# atx_power_control.net
KiCad netlist of a schematic drawn in EAGLE
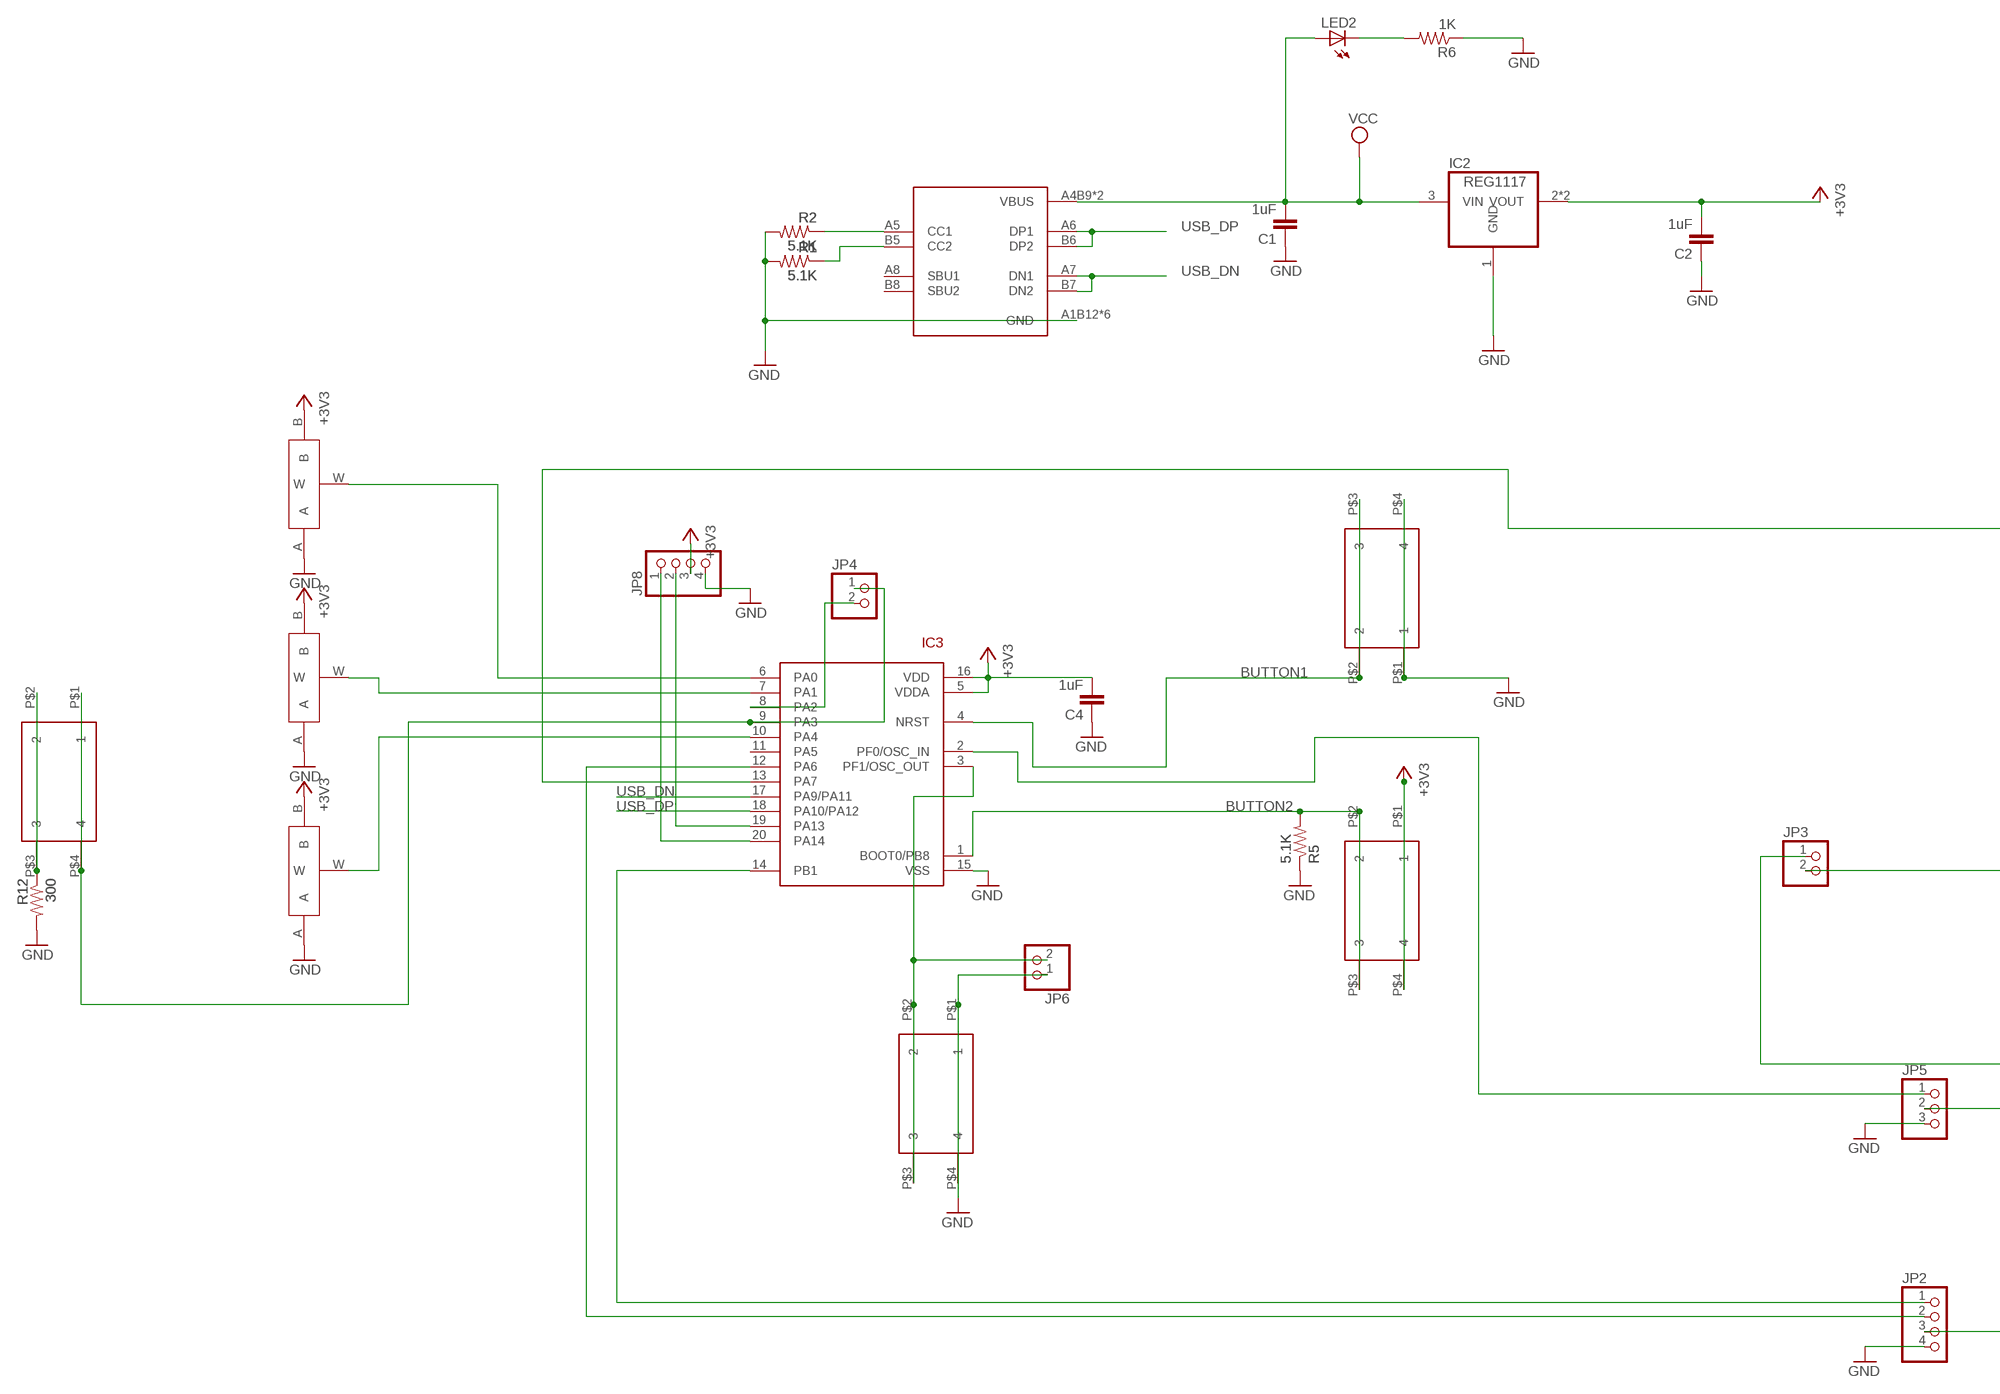
[diagram p0: schematic, sheet 1, part 1 of 2]
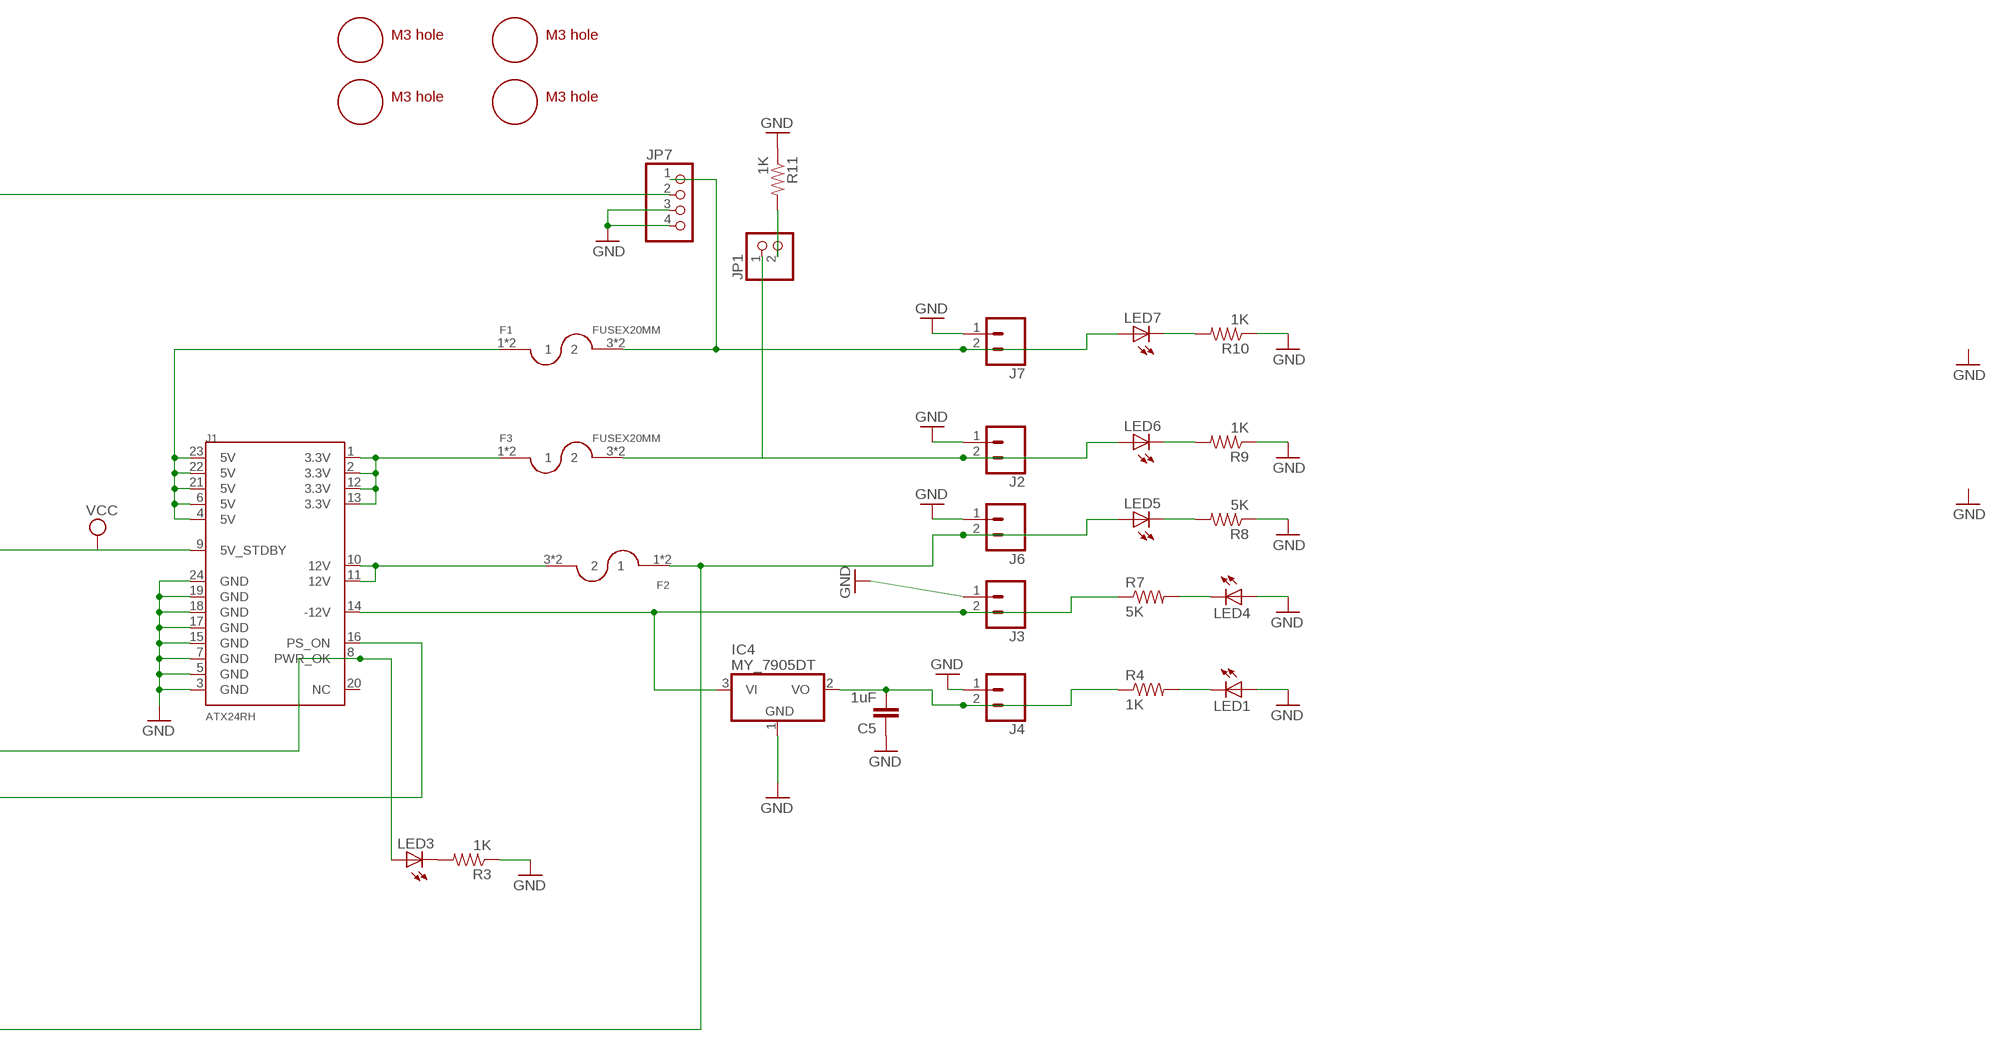
[diagram p1: schematic, sheet 1, part 2 of 2]

(export (version "E")
  (design (tool "Eeschema 10.0.6"))
  (components
    (comp (ref "C1")
      (value "1uF")
      (footprint "eagle-import:0805@1")
      (libsource (lib "eagle-import") (part "CAP0805"))
    )
    (comp (ref "C2")
      (value "1uF")
      (footprint "eagle-import:0805@1")
      (libsource (lib "eagle-import") (part "CAP0805"))
    )
    (comp (ref "C4")
      (value "1uF")
      (footprint "eagle-import:0805@1")
      (libsource (lib "eagle-import") (part "CAP0805"))
    )
    (comp (ref "C5")
      (value "1uF")
      (footprint "eagle-import:0805@1")
      (libsource (lib "eagle-import") (part "CAP0805"))
    )
    (comp (ref "F1")
      (value "FUSEX20MM")
      (footprint "eagle-import:FUSE_5MM")
      (libsource (lib "eagle-import") (part "FUSEX20MM"))
    )
    (comp (ref "F2")
      (value "FUSEX20MM")
      (footprint "eagle-import:FUSE_5MM")
      (libsource (lib "eagle-import") (part "FUSEX20MM"))
    )
    (comp (ref "F3")
      (value "FUSEX20MM")
      (footprint "eagle-import:FUSE_5MM")
      (libsource (lib "eagle-import") (part "FUSEX20MM"))
    )
    (comp (ref "IC2")
      (value "REG1117")
      (footprint "eagle-import:SOT223")
      (libsource (lib "eagle-import") (part "REG1117"))
    )
    (comp (ref "IC3")
      (value "STM32F042F4")
      (footprint "eagle-import:TSSOP20")
      (libsource (lib "eagle-import") (part "STM32F042F4"))
    )
    (comp (ref "IC4")
      (value "MY_7905DT")
      (footprint "eagle-import:ADAFRUIT_TO252")
      (libsource (lib "eagle-import") (part "MY_7905DT"))
    )
    (comp (ref "J1")
      (value "ATX24RH")
      (footprint "eagle-import:ATX24_RIGHT_ANGLE")
      (libsource (lib "eagle-import") (part "ATX24RH"))
    )
    (comp (ref "J2")
      (value "CONN_023.5MM")
      (footprint "eagle-import:SCREWTERMINAL-3.5MM-2")
      (libsource (lib "eagle-import") (part "CONN_023.5MM"))
    )
    (comp (ref "J3")
      (value "CONN_023.5MM")
      (footprint "eagle-import:SCREWTERMINAL-3.5MM-2")
      (libsource (lib "eagle-import") (part "CONN_023.5MM"))
    )
    (comp (ref "J4")
      (value "CONN_023.5MM")
      (footprint "eagle-import:SCREWTERMINAL-3.5MM-2")
      (libsource (lib "eagle-import") (part "CONN_023.5MM"))
    )
    (comp (ref "J6")
      (value "CONN_023.5MM")
      (footprint "eagle-import:SCREWTERMINAL-3.5MM-2")
      (libsource (lib "eagle-import") (part "CONN_023.5MM"))
    )
    (comp (ref "J7")
      (value "CONN_023.5MM")
      (footprint "eagle-import:SCREWTERMINAL-3.5MM-2")
      (libsource (lib "eagle-import") (part "CONN_023.5MM"))
    )
    (comp (ref "JP1")
      (value "PINHD-1X2")
      (footprint "eagle-import:1X02")
      (libsource (lib "eagle-import") (part "PINHD-1X2"))
    )
    (comp (ref "JP2")
      (value "PINHD-1X4")
      (footprint "eagle-import:1X04")
      (libsource (lib "eagle-import") (part "PINHD-1X4"))
    )
    (comp (ref "JP3")
      (value "PINHD-1X2")
      (footprint "eagle-import:1X02")
      (libsource (lib "eagle-import") (part "PINHD-1X2"))
    )
    (comp (ref "JP4")
      (value "PINHD-1X2")
      (footprint "eagle-import:1X02")
      (libsource (lib "eagle-import") (part "PINHD-1X2"))
    )
    (comp (ref "JP5")
      (value "PINHD-1X3")
      (footprint "eagle-import:1X03")
      (libsource (lib "eagle-import") (part "PINHD-1X3"))
    )
    (comp (ref "JP6")
      (value "PINHD-1X2")
      (footprint "eagle-import:1X02")
      (libsource (lib "eagle-import") (part "PINHD-1X2"))
    )
    (comp (ref "JP7")
      (value "PINHD-1X4")
      (footprint "eagle-import:1X04")
      (libsource (lib "eagle-import") (part "PINHD-1X4"))
    )
    (comp (ref "JP8")
      (value "PINHD-1X4")
      (footprint "eagle-import:1X04")
      (libsource (lib "eagle-import") (part "PINHD-1X4"))
    )
    (comp (ref "LED1")
      (value "LEDCHIP-LED0805")
      (footprint "eagle-import:CHIP-LED0805")
      (libsource (lib "eagle-import") (part "LEDCHIP-LED0805"))
    )
    (comp (ref "LED2")
      (value "LEDCHIP-LED0805")
      (footprint "eagle-import:CHIP-LED0805")
      (libsource (lib "eagle-import") (part "LEDCHIP-LED0805"))
    )
    (comp (ref "LED3")
      (value "LEDCHIP-LED0805")
      (footprint "eagle-import:CHIP-LED0805")
      (libsource (lib "eagle-import") (part "LEDCHIP-LED0805"))
    )
    (comp (ref "LED4")
      (value "LEDCHIP-LED0805")
      (footprint "eagle-import:CHIP-LED0805")
      (libsource (lib "eagle-import") (part "LEDCHIP-LED0805"))
    )
    (comp (ref "LED5")
      (value "LEDCHIP-LED0805")
      (footprint "eagle-import:CHIP-LED0805")
      (libsource (lib "eagle-import") (part "LEDCHIP-LED0805"))
    )
    (comp (ref "LED6")
      (value "LEDCHIP-LED0805")
      (footprint "eagle-import:CHIP-LED0805")
      (libsource (lib "eagle-import") (part "LEDCHIP-LED0805"))
    )
    (comp (ref "LED7")
      (value "LEDCHIP-LED0805")
      (footprint "eagle-import:CHIP-LED0805")
      (libsource (lib "eagle-import") (part "LEDCHIP-LED0805"))
    )
    (comp (ref "R1")
      (value "5.1K")
      (footprint "eagle-import:0805")
      (libsource (lib "eagle-import") (part "joyAnalog_RESISTOR0805-RES"))
    )
    (comp (ref "R2")
      (value "5.1K")
      (footprint "eagle-import:0805")
      (libsource (lib "eagle-import") (part "joyAnalog_RESISTOR0805-RES"))
    )
    (comp (ref "R3")
      (value "1K")
      (footprint "eagle-import:0805")
      (libsource (lib "eagle-import") (part "RESISTOR0805-RES"))
    )
    (comp (ref "R4")
      (value "1K")
      (footprint "eagle-import:0805")
      (libsource (lib "eagle-import") (part "RESISTOR0805-RES"))
    )
    (comp (ref "R5")
      (value "5.1K")
      (footprint "eagle-import:0805")
      (libsource (lib "eagle-import") (part "joyAnalog_RESISTOR0805-RES"))
    )
    (comp (ref "R6")
      (value "1K")
      (footprint "eagle-import:0805")
      (libsource (lib "eagle-import") (part "RESISTOR0805-RES"))
    )
    (comp (ref "R7")
      (value "5K")
      (footprint "eagle-import:0805")
      (libsource (lib "eagle-import") (part "RESISTOR0805-RES"))
    )
    (comp (ref "R8")
      (value "5K")
      (footprint "eagle-import:0805")
      (libsource (lib "eagle-import") (part "RESISTOR0805-RES"))
    )
    (comp (ref "R9")
      (value "1K")
      (footprint "eagle-import:0805")
      (libsource (lib "eagle-import") (part "RESISTOR0805-RES"))
    )
    (comp (ref "R10")
      (value "1K")
      (footprint "eagle-import:0805")
      (libsource (lib "eagle-import") (part "RESISTOR0805-RES"))
    )
    (comp (ref "R11")
      (value "1K")
      (footprint "eagle-import:0805")
      (libsource (lib "eagle-import") (part "RESISTOR0805-RES"))
    )
    (comp (ref "R12")
      (value "300")
      (footprint "eagle-import:0805")
      (libsource (lib "eagle-import") (part "joyAnalog_RESISTOR0805-RES"))
    )
    (comp (ref "SW1")
      (value "324_SW")
      (footprint "eagle-import:342_SWICH_FOOT")
      (libsource (lib "eagle-import") (part "324_SW"))
    )
    (comp (ref "SW2")
      (value "324_SW")
      (footprint "eagle-import:342_SWICH_FOOT")
      (libsource (lib "eagle-import") (part "324_SW"))
    )
    (comp (ref "SW3")
      (value "324_SW")
      (footprint "eagle-import:342_SWICH_FOOT")
      (libsource (lib "eagle-import") (part "324_SW"))
    )
    (comp (ref "SW4")
      (value "324_SW")
      (footprint "eagle-import:342_SWICH_FOOT")
      (libsource (lib "eagle-import") (part "324_SW"))
    )
    (comp (ref "U$1")
      (value "M3_MOUNTING_HOLE")
      (footprint "eagle-import:M3_MOUNTING_HOLE_PACK")
      (libsource (lib "eagle-import") (part "M3_MOUNTING_HOLE"))
    )
    (comp (ref "U$2")
      (value "M3_MOUNTING_HOLE")
      (footprint "eagle-import:M3_MOUNTING_HOLE_PACK")
      (libsource (lib "eagle-import") (part "M3_MOUNTING_HOLE"))
    )
    (comp (ref "U$3")
      (value "M3_MOUNTING_HOLE")
      (footprint "eagle-import:M3_MOUNTING_HOLE_PACK")
      (libsource (lib "eagle-import") (part "M3_MOUNTING_HOLE"))
    )
    (comp (ref "U$4")
      (value "3386P")
      (footprint "eagle-import:3386P")
      (libsource (lib "eagle-import") (part "3386P"))
    )
    (comp (ref "U$5")
      (value "3386P")
      (footprint "eagle-import:3386P")
      (libsource (lib "eagle-import") (part "3386P"))
    )
    (comp (ref "U$6")
      (value "3386P")
      (footprint "eagle-import:3386P")
      (libsource (lib "eagle-import") (part "3386P"))
    )
    (comp (ref "U$10")
      (value "M3_MOUNTING_HOLE")
      (footprint "eagle-import:M3_MOUNTING_HOLE_PACK")
      (libsource (lib "eagle-import") (part "M3_MOUNTING_HOLE"))
    )
    (comp (ref "U2")
      (value "USBC_16P")
      (footprint "eagle-import:USBC_16P_FOOT")
      (libsource (lib "eagle-import") (part "USBC_16P"))
    )
  )
  (nets
    (net (code "1") (name "+3V3") (class "Default")
      (node (ref "C2") (pin "2") (pinfunction "2_2") (pintype "passive"))
      (node (ref "C4") (pin "2") (pinfunction "2_2") (pintype "passive"))
      (node (ref "IC2") (pin "2") (pinfunction "VOUT_2") (pintype "output"))
      (node (ref "IC2") (pin "4") (pinfunction "VOUT_4") (pintype "output"))
      (node (ref "IC3") (pin "16") (pinfunction "VDD_16") (pintype "bidirectional"))
      (node (ref "IC3") (pin "5") (pinfunction "VDDA_5") (pintype "bidirectional"))
      (node (ref "JP8") (pin "3") (pinfunction "3_3") (pintype "passive"))
      (node (ref "SW4") (pin "P$1") (pinfunction "1_P$1") (pintype "bidirectional"))
      (node (ref "SW4") (pin "P$4") (pinfunction "4_P$4") (pintype "bidirectional"))
      (node (ref "U$4") (pin "B") (pinfunction "B_B") (pintype "bidirectional"))
      (node (ref "U$5") (pin "B") (pinfunction "B_B") (pintype "bidirectional"))
      (node (ref "U$6") (pin "B") (pinfunction "B_B") (pintype "bidirectional"))
    )
    (net (code "2") (name "/BUTTON1") (class "Default")
      (node (ref "IC3") (pin "4") (pinfunction "NRST_4") (pintype "bidirectional"))
      (node (ref "SW3") (pin "P$2") (pinfunction "2_P$2") (pintype "bidirectional"))
      (node (ref "SW3") (pin "P$3") (pinfunction "3_P$3") (pintype "bidirectional"))
    )
    (net (code "3") (name "/BUTTON2") (class "Default")
      (node (ref "IC3") (pin "1") (pinfunction "BOOT0/PB8_1") (pintype "bidirectional"))
      (node (ref "R5") (pin "2") (pinfunction "2_2") (pintype "passive"))
      (node (ref "SW4") (pin "P$2") (pinfunction "2_P$2") (pintype "bidirectional"))
      (node (ref "SW4") (pin "P$3") (pinfunction "3_P$3") (pintype "bidirectional"))
    )
    (net (code "4") (name "/USB_DN") (class "Default")
      (node (ref "IC3") (pin "17") (pinfunction "PA9/PA11_17") (pintype "bidirectional"))
      (node (ref "U2") (pin "A7") (pinfunction "DN1_A7") (pintype "bidirectional"))
      (node (ref "U2") (pin "B7") (pinfunction "DN2_B7") (pintype "bidirectional"))
    )
    (net (code "5") (name "/USB_DP") (class "Default")
      (node (ref "IC3") (pin "18") (pinfunction "PA10/PA12_18") (pintype "bidirectional"))
      (node (ref "U2") (pin "A6") (pinfunction "DP1_A6") (pintype "bidirectional"))
      (node (ref "U2") (pin "B6") (pinfunction "DP2_B6") (pintype "bidirectional"))
    )
    (net (code "6") (name "GND") (class "Default")
      (node (ref "C1") (pin "1") (pinfunction "1_1") (pintype "passive"))
      (node (ref "C2") (pin "1") (pinfunction "1_1") (pintype "passive"))
      (node (ref "C4") (pin "1") (pinfunction "1_1") (pintype "passive"))
      (node (ref "C5") (pin "1") (pinfunction "1_1") (pintype "passive"))
      (node (ref "IC2") (pin "1") (pinfunction "GND_1") (pintype "power_in"))
      (node (ref "IC3") (pin "15") (pinfunction "VSS_15") (pintype "bidirectional"))
      (node (ref "IC4") (pin "1") (pinfunction "GND_1") (pintype "passive"))
      (node (ref "J1") (pin "15") (pinfunction "GND_15") (pintype "bidirectional"))
      (node (ref "J1") (pin "17") (pinfunction "GND_17") (pintype "bidirectional"))
      (node (ref "J1") (pin "18") (pinfunction "GND_18") (pintype "bidirectional"))
      (node (ref "J1") (pin "19") (pinfunction "GND_19") (pintype "bidirectional"))
      (node (ref "J1") (pin "24") (pinfunction "GND_24") (pintype "bidirectional"))
      (node (ref "J1") (pin "3") (pinfunction "GND_3") (pintype "bidirectional"))
      (node (ref "J1") (pin "5") (pinfunction "GND_5") (pintype "bidirectional"))
      (node (ref "J1") (pin "7") (pinfunction "GND_7") (pintype "bidirectional"))
      (node (ref "J2") (pin "1") (pinfunction "1_1") (pintype "passive"))
      (node (ref "J3") (pin "1") (pinfunction "1_1") (pintype "passive"))
      (node (ref "J4") (pin "1") (pinfunction "1_1") (pintype "passive"))
      (node (ref "J6") (pin "1") (pinfunction "1_1") (pintype "passive"))
      (node (ref "J7") (pin "1") (pinfunction "1_1") (pintype "passive"))
      (node (ref "JP2") (pin "4") (pinfunction "4_4") (pintype "passive"))
      (node (ref "JP5") (pin "3") (pinfunction "3_3") (pintype "passive"))
      (node (ref "JP6") (pin "1") (pinfunction "1_1") (pintype "passive"))
      (node (ref "JP7") (pin "3") (pinfunction "3_3") (pintype "passive"))
      (node (ref "JP7") (pin "4") (pinfunction "4_4") (pintype "passive"))
      (node (ref "JP8") (pin "4") (pinfunction "4_4") (pintype "passive"))
      (node (ref "LED1") (pin "A") (pinfunction "A_A") (pintype "passive"))
      (node (ref "LED4") (pin "A") (pinfunction "A_A") (pintype "passive"))
      (node (ref "R1") (pin "2") (pinfunction "2_2") (pintype "passive"))
      (node (ref "R10") (pin "1") (pinfunction "1_1") (pintype "passive"))
      (node (ref "R11") (pin "1") (pinfunction "1_1") (pintype "passive"))
      (node (ref "R12") (pin "2") (pinfunction "2_2") (pintype "passive"))
      (node (ref "R2") (pin "2") (pinfunction "2_2") (pintype "passive"))
      (node (ref "R3") (pin "1") (pinfunction "1_1") (pintype "passive"))
      (node (ref "R5") (pin "1") (pinfunction "1_1") (pintype "passive"))
      (node (ref "R6") (pin "1") (pinfunction "1_1") (pintype "passive"))
      (node (ref "R8") (pin "1") (pinfunction "1_1") (pintype "passive"))
      (node (ref "R9") (pin "1") (pinfunction "1_1") (pintype "passive"))
      (node (ref "SW1") (pin "P$1") (pinfunction "1_P$1") (pintype "bidirectional"))
      (node (ref "SW1") (pin "P$4") (pinfunction "4_P$4") (pintype "bidirectional"))
      (node (ref "SW3") (pin "P$1") (pinfunction "1_P$1") (pintype "bidirectional"))
      (node (ref "SW3") (pin "P$4") (pinfunction "4_P$4") (pintype "bidirectional"))
      (node (ref "U$4") (pin "A") (pinfunction "A_A") (pintype "bidirectional"))
      (node (ref "U$5") (pin "A") (pinfunction "A_A") (pintype "bidirectional"))
      (node (ref "U$6") (pin "A") (pinfunction "A_A") (pintype "bidirectional"))
      (node (ref "U2") (pin "A1B12") (pinfunction "GND_A1B12") (pintype "bidirectional"))
      (node (ref "U2") (pin "B11A12") (pinfunction "GND_B11A12") (pintype "bidirectional"))
      (node (ref "U2") (pin "P$13") (pinfunction "GND_P$13") (pintype "bidirectional"))
      (node (ref "U2") (pin "P$14") (pinfunction "GND_P$14") (pintype "bidirectional"))
      (node (ref "U2") (pin "P$15") (pinfunction "GND_P$15") (pintype "bidirectional"))
      (node (ref "U2") (pin "P$16") (pinfunction "GND_P$16") (pintype "bidirectional"))
    )
    (net (code "7") (name "Net-(F1-1-Pad2)") (class "Default")
      (node (ref "F1") (pin "1") (pinfunction "1_1") (pintype "bidirectional"))
      (node (ref "F1") (pin "2") (pinfunction "1_2") (pintype "bidirectional"))
      (node (ref "J1") (pin "21") (pinfunction "5V_21") (pintype "bidirectional"))
      (node (ref "J1") (pin "22") (pinfunction "5V_22") (pintype "bidirectional"))
      (node (ref "J1") (pin "23") (pinfunction "5V_23") (pintype "bidirectional"))
      (node (ref "J1") (pin "4") (pinfunction "5V_4") (pintype "bidirectional"))
      (node (ref "J1") (pin "6") (pinfunction "5V_6") (pintype "bidirectional"))
    )
    (net (code "8") (name "Net-(F1-2-Pad3)") (class "Default")
      (node (ref "F1") (pin "3") (pinfunction "2_3") (pintype "bidirectional"))
      (node (ref "F1") (pin "4") (pinfunction "2_4") (pintype "bidirectional"))
      (node (ref "J7") (pin "2") (pinfunction "2_2") (pintype "passive"))
      (node (ref "JP7") (pin "1") (pinfunction "1_1") (pintype "passive"))
      (node (ref "LED7") (pin "A") (pinfunction "A_A") (pintype "passive"))
    )
    (net (code "9") (name "Net-(F2-1-Pad2)") (class "Default")
      (node (ref "F2") (pin "1") (pinfunction "1_1") (pintype "bidirectional"))
      (node (ref "F2") (pin "2") (pinfunction "1_2") (pintype "bidirectional"))
      (node (ref "J6") (pin "2") (pinfunction "2_2") (pintype "passive"))
      (node (ref "JP2") (pin "3") (pinfunction "3_3") (pintype "passive"))
      (node (ref "LED5") (pin "A") (pinfunction "A_A") (pintype "passive"))
    )
    (net (code "10") (name "Net-(F2-2-Pad3)") (class "Default")
      (node (ref "F2") (pin "3") (pinfunction "2_3") (pintype "bidirectional"))
      (node (ref "F2") (pin "4") (pinfunction "2_4") (pintype "bidirectional"))
      (node (ref "J1") (pin "10") (pinfunction "12V_10") (pintype "bidirectional"))
      (node (ref "J1") (pin "11") (pinfunction "12V_11") (pintype "bidirectional"))
    )
    (net (code "11") (name "Net-(F3-1-Pad2)") (class "Default")
      (node (ref "F3") (pin "1") (pinfunction "1_1") (pintype "bidirectional"))
      (node (ref "F3") (pin "2") (pinfunction "1_2") (pintype "bidirectional"))
      (node (ref "J1") (pin "1") (pinfunction "3.3V_1") (pintype "bidirectional"))
      (node (ref "J1") (pin "12") (pinfunction "3.3V_12") (pintype "bidirectional"))
      (node (ref "J1") (pin "13") (pinfunction "3.3V_13") (pintype "bidirectional"))
      (node (ref "J1") (pin "2") (pinfunction "3.3V_2") (pintype "bidirectional"))
    )
    (net (code "12") (name "Net-(F3-2-Pad3)") (class "Default")
      (node (ref "F3") (pin "3") (pinfunction "2_3") (pintype "bidirectional"))
      (node (ref "F3") (pin "4") (pinfunction "2_4") (pintype "bidirectional"))
      (node (ref "J2") (pin "2") (pinfunction "2_2") (pintype "passive"))
      (node (ref "JP1") (pin "1") (pinfunction "1_1") (pintype "passive"))
      (node (ref "LED6") (pin "A") (pinfunction "A_A") (pintype "passive"))
    )
    (net (code "13") (name "Net-(IC3-PA0)") (class "Default")
      (node (ref "IC3") (pin "6") (pinfunction "PA0_6") (pintype "bidirectional"))
      (node (ref "U$4") (pin "W") (pinfunction "W_W") (pintype "bidirectional"))
    )
    (net (code "14") (name "Net-(IC3-PA1)") (class "Default")
      (node (ref "IC3") (pin "7") (pinfunction "PA1_7") (pintype "bidirectional"))
      (node (ref "U$5") (pin "W") (pinfunction "W_W") (pintype "bidirectional"))
    )
    (net (code "15") (name "Net-(IC3-PA2)") (class "Default")
      (node (ref "IC3") (pin "8") (pinfunction "PA2_8") (pintype "bidirectional"))
      (node (ref "JP4") (pin "2") (pinfunction "2_2") (pintype "passive"))
    )
    (net (code "16") (name "Net-(IC3-PA3)") (class "Default")
      (node (ref "IC3") (pin "9") (pinfunction "PA3_9") (pintype "bidirectional"))
      (node (ref "JP4") (pin "1") (pinfunction "1_1") (pintype "passive"))
      (node (ref "SW2") (pin "P$1") (pinfunction "1_P$1") (pintype "bidirectional"))
      (node (ref "SW2") (pin "P$4") (pinfunction "4_P$4") (pintype "bidirectional"))
    )
    (net (code "17") (name "Net-(IC3-PA4)") (class "Default")
      (node (ref "IC3") (pin "10") (pinfunction "PA4_10") (pintype "bidirectional"))
      (node (ref "U$6") (pin "W") (pinfunction "W_W") (pintype "bidirectional"))
    )
    (net (code "18") (name "Net-(IC3-PA6)") (class "Default")
      (node (ref "IC3") (pin "12") (pinfunction "PA6_12") (pintype "bidirectional"))
      (node (ref "JP2") (pin "2") (pinfunction "2_2") (pintype "passive"))
    )
    (net (code "19") (name "Net-(IC3-PA7)") (class "Default")
      (node (ref "IC3") (pin "13") (pinfunction "PA7_13") (pintype "bidirectional"))
      (node (ref "JP7") (pin "2") (pinfunction "2_2") (pintype "passive"))
    )
    (net (code "20") (name "Net-(IC3-PA13)") (class "Default")
      (node (ref "IC3") (pin "19") (pinfunction "PA13_19") (pintype "bidirectional"))
      (node (ref "JP8") (pin "2") (pinfunction "2_2") (pintype "passive"))
    )
    (net (code "21") (name "Net-(IC3-PA14)") (class "Default")
      (node (ref "IC3") (pin "20") (pinfunction "PA14_20") (pintype "bidirectional"))
      (node (ref "JP8") (pin "1") (pinfunction "1_1") (pintype "passive"))
    )
    (net (code "22") (name "Net-(IC3-PB1)") (class "Default")
      (node (ref "IC3") (pin "14") (pinfunction "PB1_14") (pintype "bidirectional"))
      (node (ref "JP2") (pin "1") (pinfunction "1_1") (pintype "passive"))
    )
    (net (code "23") (name "Net-(IC3-PF0{slash}OSC_IN)") (class "Default")
      (node (ref "IC3") (pin "2") (pinfunction "PF0/OSC_IN_2") (pintype "bidirectional"))
      (node (ref "JP5") (pin "1") (pinfunction "1_1") (pintype "passive"))
    )
    (net (code "24") (name "Net-(IC3-PF1{slash}OSC_OUT)") (class "Default")
      (node (ref "IC3") (pin "3") (pinfunction "PF1/OSC_OUT_3") (pintype "bidirectional"))
      (node (ref "JP6") (pin "2") (pinfunction "2_2") (pintype "passive"))
      (node (ref "SW1") (pin "P$2") (pinfunction "2_P$2") (pintype "bidirectional"))
      (node (ref "SW1") (pin "P$3") (pinfunction "3_P$3") (pintype "bidirectional"))
    )
    (net (code "25") (name "Net-(IC4-VI)") (class "Default")
      (node (ref "IC4") (pin "3") (pinfunction "VI_3") (pintype "input"))
      (node (ref "J1") (pin "14") (pinfunction "-12V_14") (pintype "bidirectional"))
      (node (ref "J3") (pin "2") (pinfunction "2_2") (pintype "passive"))
      (node (ref "R7") (pin "1") (pinfunction "1_1") (pintype "passive"))
    )
    (net (code "26") (name "Net-(IC4-VO)") (class "Default")
      (node (ref "C5") (pin "2") (pinfunction "2_2") (pintype "passive"))
      (node (ref "IC4") (pin "2") (pinfunction "VO_2") (pintype "passive"))
      (node (ref "J4") (pin "2") (pinfunction "2_2") (pintype "passive"))
      (node (ref "R4") (pin "1") (pinfunction "1_1") (pintype "passive"))
    )
    (net (code "27") (name "Net-(J1-PS_ON)") (class "Default")
      (node (ref "J1") (pin "16") (pinfunction "PS_ON_16") (pintype "bidirectional"))
      (node (ref "JP5") (pin "2") (pinfunction "2_2") (pintype "passive"))
    )
    (net (code "28") (name "Net-(J1-PWR_OK)") (class "Default")
      (node (ref "J1") (pin "8") (pinfunction "PWR_OK_8") (pintype "bidirectional"))
      (node (ref "JP3") (pin "1") (pinfunction "1_1") (pintype "passive"))
      (node (ref "LED3") (pin "A") (pinfunction "A_A") (pintype "passive"))
    )
    (net (code "29") (name "Net-(JP1-Pad2)") (class "Default")
      (node (ref "JP1") (pin "2") (pinfunction "2_2") (pintype "passive"))
      (node (ref "R11") (pin "2") (pinfunction "2_2") (pintype "passive"))
    )
    (net (code "30") (name "Net-(LED1-PadC)") (class "Default")
      (node (ref "LED1") (pin "C") (pinfunction "C_C") (pintype "passive"))
      (node (ref "R4") (pin "2") (pinfunction "2_2") (pintype "passive"))
    )
    (net (code "31") (name "Net-(LED2-PadC)") (class "Default")
      (node (ref "LED2") (pin "C") (pinfunction "C_C") (pintype "passive"))
      (node (ref "R6") (pin "2") (pinfunction "2_2") (pintype "passive"))
    )
    (net (code "32") (name "Net-(LED3-PadC)") (class "Default")
      (node (ref "LED3") (pin "C") (pinfunction "C_C") (pintype "passive"))
      (node (ref "R3") (pin "2") (pinfunction "2_2") (pintype "passive"))
    )
    (net (code "33") (name "Net-(LED4-PadC)") (class "Default")
      (node (ref "LED4") (pin "C") (pinfunction "C_C") (pintype "passive"))
      (node (ref "R7") (pin "2") (pinfunction "2_2") (pintype "passive"))
    )
    (net (code "34") (name "Net-(LED5-PadC)") (class "Default")
      (node (ref "LED5") (pin "C") (pinfunction "C_C") (pintype "passive"))
      (node (ref "R8") (pin "2") (pinfunction "2_2") (pintype "passive"))
    )
    (net (code "35") (name "Net-(LED6-PadC)") (class "Default")
      (node (ref "LED6") (pin "C") (pinfunction "C_C") (pintype "passive"))
      (node (ref "R9") (pin "2") (pinfunction "2_2") (pintype "passive"))
    )
    (net (code "36") (name "Net-(LED7-PadC)") (class "Default")
      (node (ref "LED7") (pin "C") (pinfunction "C_C") (pintype "passive"))
      (node (ref "R10") (pin "2") (pinfunction "2_2") (pintype "passive"))
    )
    (net (code "37") (name "Net-(SW2-2)") (class "Default")
      (node (ref "R12") (pin "1") (pinfunction "1_1") (pintype "passive"))
      (node (ref "SW2") (pin "P$2") (pinfunction "2_P$2") (pintype "bidirectional"))
      (node (ref "SW2") (pin "P$3") (pinfunction "3_P$3") (pintype "bidirectional"))
    )
    (net (code "38") (name "Net-(U2-CC1)") (class "Default")
      (node (ref "R2") (pin "1") (pinfunction "1_1") (pintype "passive"))
      (node (ref "U2") (pin "A5") (pinfunction "CC1_A5") (pintype "bidirectional"))
    )
    (net (code "39") (name "Net-(U2-CC2)") (class "Default")
      (node (ref "R1") (pin "1") (pinfunction "1_1") (pintype "passive"))
      (node (ref "U2") (pin "B5") (pinfunction "CC2_B5") (pintype "bidirectional"))
    )
    (net (code "40") (name "VCC") (class "Default")
      (node (ref "C1") (pin "2") (pinfunction "2_2") (pintype "passive"))
      (node (ref "IC2") (pin "3") (pinfunction "VIN_3") (pintype "input"))
      (node (ref "J1") (pin "9") (pinfunction "5V_STDBY_9") (pintype "bidirectional"))
      (node (ref "JP3") (pin "2") (pinfunction "2_2") (pintype "passive"))
      (node (ref "LED2") (pin "A") (pinfunction "A_A") (pintype "passive"))
      (node (ref "U2") (pin "A4B9") (pinfunction "VBUS_A4B9") (pintype "bidirectional"))
      (node (ref "U2") (pin "B4A9") (pinfunction "VBUS_B4A9") (pintype "bidirectional"))
    )
    (net (code "41") (name "unconnected-(IC3-PA5-Pad11)") (class "Default")
      (node (ref "IC3") (pin "11") (pinfunction "PA5_11") (pintype "bidirectional"))
    )
    (net (code "42") (name "unconnected-(J1-NC-Pad20)") (class "Default")
      (node (ref "J1") (pin "20") (pinfunction "NC_20") (pintype "bidirectional"))
    )
    (net (code "43") (name "unconnected-(U2-SBU1-PadA8)") (class "Default")
      (node (ref "U2") (pin "A8") (pinfunction "SBU1_A8") (pintype "bidirectional"))
    )
    (net (code "44") (name "unconnected-(U2-SBU2-PadB8)") (class "Default")
      (node (ref "U2") (pin "B8") (pinfunction "SBU2_B8") (pintype "bidirectional"))
    )
  )
)
